# Sensors.net
KiCad netlist of a schematic drawn in Altium Designer
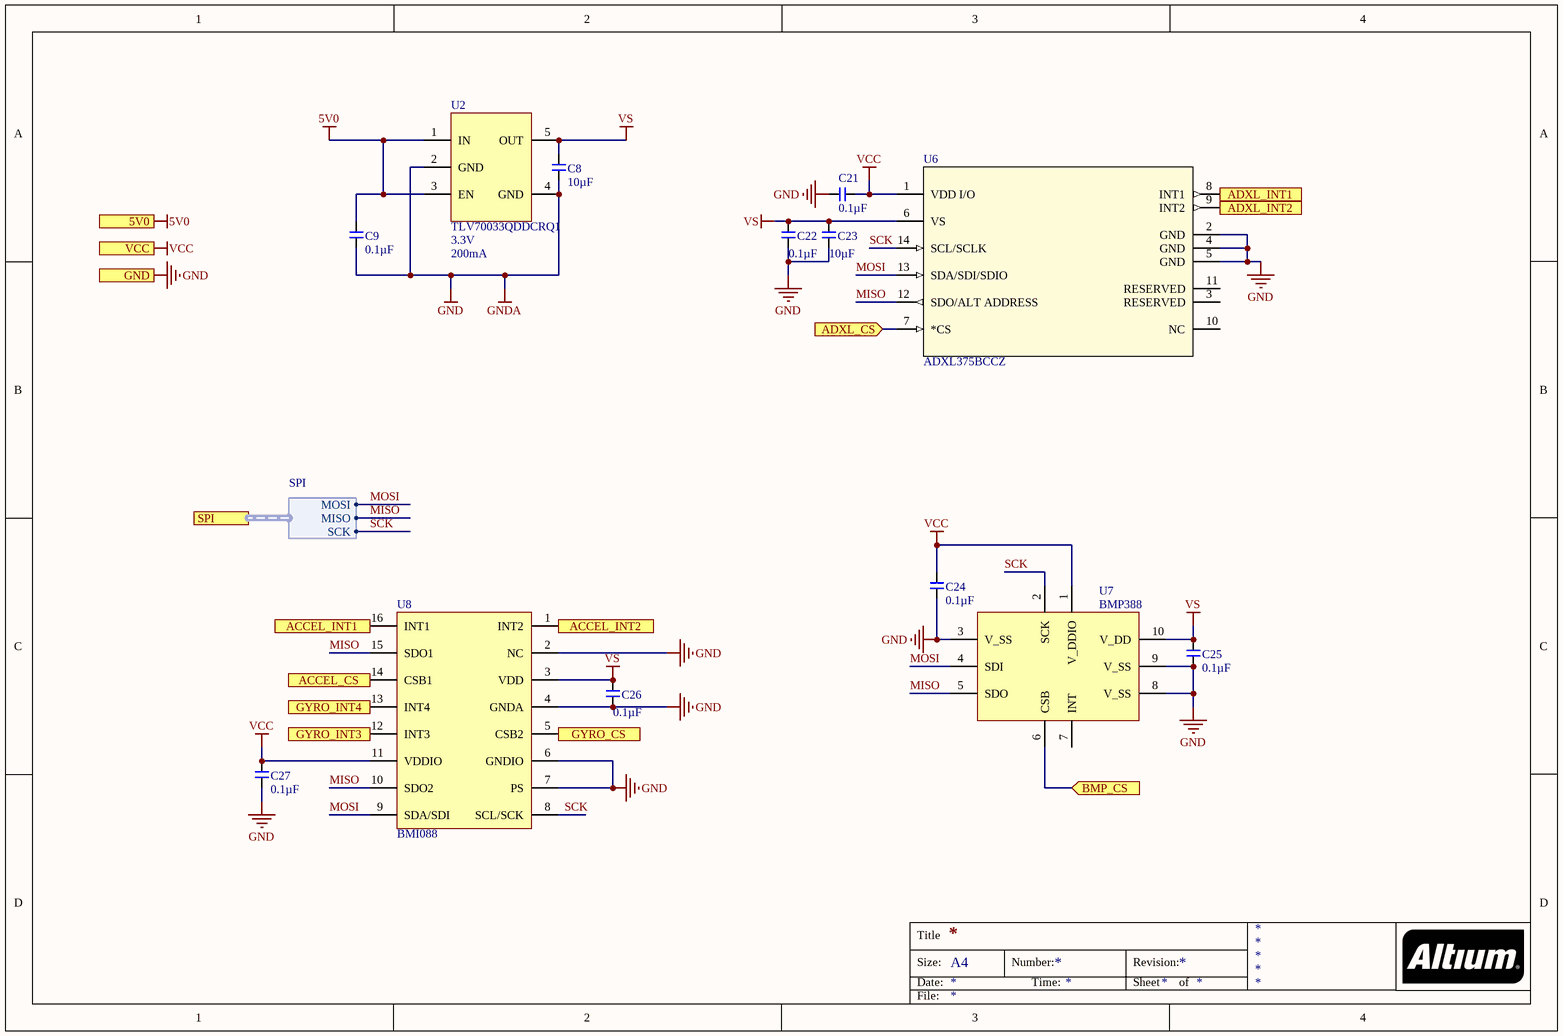
[diagram p0: Sensors.SchDoc]

(export (version "E")
  (design (tool "Eeschema 10.0.6"))
  (components
    (comp (ref "C8")
      (value "__template_cap")
      (footprint "C0603")
      (fields
        (field (name "CAPACITANCE (SHORTHAND)") "10µF")
        (field (name "MANUFACTURER") "Murata Electronics North America")
      )
      (libsource (lib "passives") (part "__template_cap"))
    )
    (comp (ref "C9")
      (value "__template_cap")
      (footprint "C0603")
      (fields
        (field (name "CAPACITANCE (SHORTHAND)") "0.1µF")
        (field (name "MANUFACTURER") "Murata Electronics North America")
      )
      (libsource (lib "passives") (part "__template_cap"))
    )
    (comp (ref "C21")
      (value "__template_cap")
      (footprint "C0603")
      (fields
        (field (name "CAPACITANCE (SHORTHAND)") "0.1µF")
        (field (name "MANUFACTURER") "Murata Electronics North America")
      )
      (libsource (lib "passives") (part "__template_cap"))
    )
    (comp (ref "C22")
      (value "__template_cap")
      (footprint "C0603")
      (fields
        (field (name "CAPACITANCE (SHORTHAND)") "0.1µF")
        (field (name "MANUFACTURER") "Murata Electronics North America")
      )
      (libsource (lib "passives") (part "__template_cap"))
    )
    (comp (ref "C23")
      (value "__template_cap")
      (footprint "C0603")
      (fields
        (field (name "CAPACITANCE (SHORTHAND)") "10µF")
        (field (name "MANUFACTURER") "Murata Electronics North America")
      )
      (libsource (lib "passives") (part "__template_cap"))
    )
    (comp (ref "C24")
      (value "__template_cap")
      (footprint "C0603")
      (fields
        (field (name "CAPACITANCE (SHORTHAND)") "0.1µF")
        (field (name "MANUFACTURER") "Murata Electronics North America")
      )
      (libsource (lib "passives") (part "__template_cap"))
    )
    (comp (ref "C25")
      (value "__template_cap")
      (footprint "C0603")
      (fields
        (field (name "CAPACITANCE (SHORTHAND)") "0.1µF")
        (field (name "MANUFACTURER") "Murata Electronics North America")
      )
      (libsource (lib "passives") (part "__template_cap"))
    )
    (comp (ref "C26")
      (value "__template_cap")
      (footprint "C0603")
      (fields
        (field (name "CAPACITANCE (SHORTHAND)") "0.1µF")
        (field (name "MANUFACTURER") "Murata Electronics North America")
      )
      (libsource (lib "passives") (part "__template_cap"))
    )
    (comp (ref "C27")
      (value "__template_cap")
      (footprint "C0603")
      (fields
        (field (name "CAPACITANCE (SHORTHAND)") "0.1µF")
        (field (name "MANUFACTURER") "Murata Electronics North America")
      )
      (libsource (lib "passives") (part "__template_cap"))
    )
    (comp (ref "U2")
      (value "REG102GA-3.3")
      (footprint "5SOT23")
      (description "IC REG LDO 3.3V .2A SOT23-5")
      (fields
        (field (name "MANUFACTURER") "Texas Instruments")
        (field (name "MANUFACTURER PART NUMBER") "TLV70033QDDCRQ1")
        (field (name "VOLTAGE - OUTPUT") "3.3V")
        (field (name "CURRENT - OUTPUT") "200mA")
      )
      (libsource (lib "SSI") (part "LDO_TLV70033QDDCRQ1"))
    )
    (comp (ref "U6")
      (value "ADXL375BCCZ")
      (footprint "LGA_CC-14-1")
      (description "200G Accelcerometer")
      (libsource (lib "SSI") (part "ADXL375BCCZ"))
    )
    (comp (ref "U7")
      (value "BMP388")
      (footprint "8 pin LGA")
      (description "Pressure Sensor 4.35 PSI ~ 18.13 PSI (30 kPa ~ 125 kPa) Absolute 10-WFLGA")
      (fields (field (name "MANUFACTURER") "Bosch Sensortec"))
      (libsource (lib "SSI") (part "BMP388"))
    )
    (comp (ref "U8")
      (value "BMI088")
      (footprint "BMI088")
      (description "Bosch BMI088")
      (libsource (lib "sensor") (part "IMU_BMI088"))
    )
  )
  (nets
    (net (code "2") (name "/ACCEL_CS") (class "Default")
      (node (ref "U8") (pin "14") (pinfunction "CSB1_14") (pintype "passive"))
    )
    (net (code "3") (name "/ACCEL_INT1") (class "Default")
      (node (ref "U8") (pin "16") (pinfunction "INT1_16") (pintype "passive"))
    )
    (net (code "4") (name "/ACCEL_INT2") (class "Default")
      (node (ref "U8") (pin "1") (pinfunction "INT2_1") (pintype "passive"))
    )
    (net (code "5") (name "/ADXL_CS") (class "Default")
      (node (ref "U6") (pin "7") (pinfunction "*CS_7") (pintype "input"))
    )
    (net (code "6") (name "/ADXL_INT1") (class "Default")
      (node (ref "U6") (pin "8") (pinfunction "INT1_8") (pintype "output"))
    )
    (net (code "7") (name "/ADXL_INT2") (class "Default")
      (node (ref "U6") (pin "9") (pinfunction "INT2_9") (pintype "output"))
    )
    (net (code "8") (name "/BMP_CS") (class "Default")
      (node (ref "U7") (pin "6") (pinfunction "CSB_6") (pintype "passive"))
    )
    (net (code "9") (name "/GYRO_CS") (class "Default")
      (node (ref "U8") (pin "5") (pinfunction "CSB2_5") (pintype "passive"))
    )
    (net (code "10") (name "/GYRO_INT3") (class "Default")
      (node (ref "U8") (pin "12") (pinfunction "INT3_12") (pintype "passive"))
    )
    (net (code "11") (name "/GYRO_INT4") (class "Default")
      (node (ref "U8") (pin "13") (pinfunction "INT4_13") (pintype "passive"))
    )
    (net (code "12") (name "/MISO") (class "Default")
      (node (ref "U6") (pin "12") (pinfunction "SDO/ALT_ADDRESS_12") (pintype "output"))
      (node (ref "U7") (pin "5") (pinfunction "SDO_5") (pintype "passive"))
      (node (ref "U8") (pin "10") (pinfunction "SDO2_10") (pintype "passive"))
      (node (ref "U8") (pin "15") (pinfunction "SDO1_15") (pintype "passive"))
    )
    (net (code "13") (name "/MOSI") (class "Default")
      (node (ref "U6") (pin "13") (pinfunction "SDA/SDI/SDIO_13") (pintype "input"))
      (node (ref "U7") (pin "4") (pinfunction "SDI_4") (pintype "passive"))
      (node (ref "U8") (pin "9") (pinfunction "SDA/SDI_9") (pintype "passive"))
    )
    (net (code "14") (name "/SCK") (class "Default")
      (node (ref "U6") (pin "14") (pinfunction "SCL/SCLK_14") (pintype "input"))
      (node (ref "U7") (pin "2") (pinfunction "SCK_2") (pintype "passive"))
      (node (ref "U8") (pin "8") (pinfunction "SCL/SCK_8") (pintype "passive"))
    )
    (net (code "16") (name "5V0") (class "Default")
      (node (ref "C9") (pin "1") (pintype "passive"))
      (node (ref "U2") (pin "1") (pinfunction "IN_1") (pintype "passive"))
      (node (ref "U2") (pin "3") (pinfunction "EN_3") (pintype "passive"))
    )
    (net (code "17") (name "GND") (class "Default")
      (node (ref "C21") (pin "2") (pintype "passive"))
      (node (ref "C22") (pin "1") (pintype "passive"))
      (node (ref "C23") (pin "2") (pintype "passive"))
      (node (ref "C24") (pin "2") (pintype "passive"))
      (node (ref "C25") (pin "2") (pintype "passive"))
      (node (ref "C26") (pin "2") (pintype "passive"))
      (node (ref "C27") (pin "2") (pintype "passive"))
      (node (ref "C8") (pin "2") (pintype "passive"))
      (node (ref "C9") (pin "2") (pintype "passive"))
      (node (ref "U2") (pin "2") (pinfunction "GND_2") (pintype "passive"))
      (node (ref "U2") (pin "4") (pinfunction "GND_4") (pintype "passive"))
      (node (ref "U6") (pin "2") (pinfunction "GND_2") (pintype "power_in"))
      (node (ref "U6") (pin "4") (pinfunction "GND_4") (pintype "power_in"))
      (node (ref "U6") (pin "5") (pinfunction "GND_5") (pintype "power_in"))
      (node (ref "U7") (pin "3") (pinfunction "V_SS_3") (pintype "passive"))
      (node (ref "U7") (pin "8") (pinfunction "V_SS_8") (pintype "passive"))
      (node (ref "U7") (pin "9") (pinfunction "V_SS_9") (pintype "passive"))
      (node (ref "U8") (pin "2") (pinfunction "NC_2") (pintype "passive"))
      (node (ref "U8") (pin "4") (pinfunction "GNDA_4") (pintype "passive"))
      (node (ref "U8") (pin "6") (pinfunction "GNDIO_6") (pintype "passive"))
      (node (ref "U8") (pin "7") (pinfunction "PS_7") (pintype "passive"))
    )
    (net (code "18") (name "VCC") (class "Default")
      (node (ref "C21") (pin "1") (pintype "passive"))
      (node (ref "C24") (pin "1") (pintype "passive"))
      (node (ref "C27") (pin "1") (pintype "passive"))
      (node (ref "U6") (pin "1") (pinfunction "VDD_I/O_1") (pintype "power_in"))
      (node (ref "U7") (pin "1") (pinfunction "V_DDIO_1") (pintype "passive"))
      (node (ref "U8") (pin "11") (pinfunction "VDDIO_11") (pintype "passive"))
    )
    (net (code "19") (name "VS") (class "Default")
      (node (ref "C22") (pin "2") (pintype "passive"))
      (node (ref "C23") (pin "1") (pintype "passive"))
      (node (ref "C25") (pin "1") (pintype "passive"))
      (node (ref "C26") (pin "1") (pintype "passive"))
      (node (ref "C8") (pin "1") (pintype "passive"))
      (node (ref "U2") (pin "5") (pinfunction "OUT_5") (pintype "passive"))
      (node (ref "U6") (pin "6") (pinfunction "VS_6") (pintype "power_in"))
      (node (ref "U7") (pin "10") (pinfunction "V_DD_10") (pintype "passive"))
      (node (ref "U8") (pin "3") (pinfunction "VDD_3") (pintype "passive"))
    )
    (net (code "20") (name "unconnected-(U6-NC-Pad10)") (class "Default")
      (node (ref "U6") (pin "10") (pinfunction "NC_10") (pintype "passive"))
    )
    (net (code "21") (name "unconnected-(U6-RESERVED-Pad3)") (class "Default")
      (node (ref "U6") (pin "3") (pinfunction "RESERVED_3") (pintype "passive"))
    )
    (net (code "22") (name "unconnected-(U6-RESERVED-Pad11)") (class "Default")
      (node (ref "U6") (pin "11") (pinfunction "RESERVED_11") (pintype "passive"))
    )
    (net (code "23") (name "unconnected-(U7-INT-Pad7)") (class "Default")
      (node (ref "U7") (pin "7") (pinfunction "INT_7") (pintype "passive"))
    )
  )
)
